# Power.net
KiCad netlist of a schematic drawn in Altium Designer
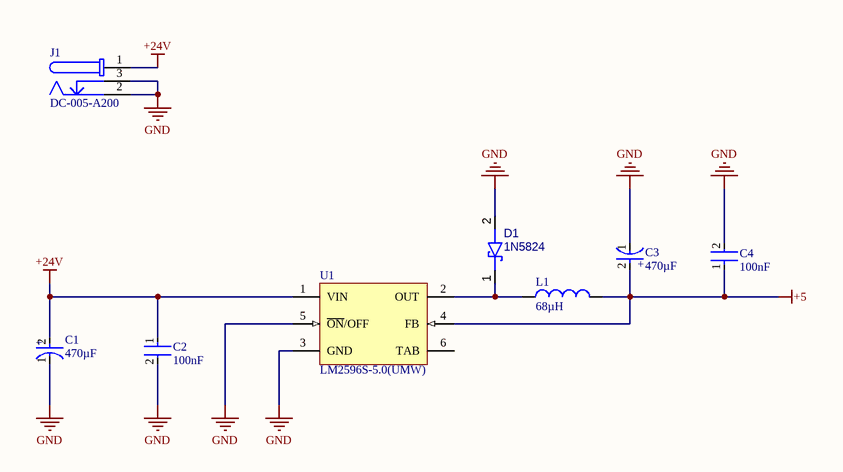
[diagram p0: Power.SchDoc]

(export (version "E")
  (design (tool "Eeschema 10.0.6"))
  (components
    (comp (ref "C1")
      (value "470µF")
      (footprint "FP-A750MV227M1HAAE020-MFG")
      (fields
        (field (name "TOLERANCE") "20%")
        (field (name "MANUFACTURER") "AISHI(Aihua Group)")
        (field (name "MFR.PART #") "ERS1VM471G16OT")
      )
      (libsource (lib "Hood") (part "a00bbbee19879c290e62620ae7e47b1"))
    )
    (comp (ref "C2")
      (value "100nF")
      (footprint "FP-CC0603-DA-IPC_B")
      (description "Multilayer Ceramic Capacitor, CC Series, 0.1 - F, - 10%, X7R, 50 V, 0603 [1608 Metric]")
      (fields (field (name "VOLTAGE") "50V") (field (name "TOLERANCE") "10%"))
      (libsource (lib "Hood") (part "11868f565c42a9108669ba33697ecf6"))
    )
    (comp (ref "C3")
      (value "470µF")
      (footprint "FP-A750MV227M1HAAE020-MFG")
      (fields (field (name "TOLERANCE") "20%") (field (name "Comment") "ERS1VM471G16OT"))
      (libsource (lib "Hood") (part "a00bbbee19879c290e62620ae7e47b1"))
    )
    (comp (ref "C4")
      (value "100nF")
      (footprint "FP-CC0603-DA-IPC_B")
      (description "Multilayer Ceramic Capacitor, CC Series, 0.1 - F, - 10%, X7R, 50 V, 0603 [1608 Metric]")
      (fields (field (name "VOLTAGE") "50V") (field (name "TOLERANCE") "10%"))
      (libsource (lib "Hood") (part "11868f565c42a9108669ba33697ecf6"))
    )
    (comp (ref "D1")
      (value "1N5824")
      (footprint "FP-017AF-MFG")
      (description "-55℃~+150℃ 150A 30V 500uA@30V 550mV@5A 5A Independent DO-201AD Schottky Diodes ROHS")
      (fields (field (name "MANUFACTURER") "FUXINSEMI") (field (name "JLCPCB PART #") "C7503125"))
      (libsource (lib "Hood") (part "DIODE-SKY-2"))
    )
    (comp (ref "J1")
      (value "DC-005-A200")
      (footprint "694108301002")
      (description "-20℃~+70℃ 2mm 30V 3A 6.4mm DC Power Jack Right Angle 插件 DC Power Connectors ROHS")
      (fields (field (name "JLCPCB PART #") "C720557") (field (name "MANUFACTURER") "XUNPU"))
      (libsource (lib "Hood") (part "DC Power Jack"))
    )
    (comp (ref "L1")
      (value "68µH")
      (footprint "CAPM115100X500N")
      (description "240mΩ 3A 4A 68uH Molded Inductor ±20% SMD,11.5x10mm Power Inductors ROHS")
      (fields (field (name "JLCPCB PART #") "C497902") (field (name "MFR.PART #") "YSPI1050-680M"))
      (libsource (lib "Hood") (part "IND-2"))
    )
    (comp (ref "U1")
      (value "LM2596S-5.0(UMW)")
      (footprint "KTT0005B_L")
      (fields
        (field (name "MANUFACTURER") "UMW(Youtai Semiconductor Co., Ltd.)")
        (field (name "JLCPCB PART #") "C347421")
      )
      (libsource (lib "Hood") (part "PM-REG-LM2575HVS-12"))
    )
  )
  (nets
    (net (code "1") (name "+5") (class "Default")
      (node (ref "C3") (pin "2") (pinfunction "A_2") (pintype "passive"))
      (node (ref "C4") (pin "1") (pinfunction "1_1") (pintype "passive"))
      (node (ref "L1") (pin "2") (pinfunction "2_2") (pintype "passive"))
      (node (ref "U1") (pin "4") (pinfunction "FB_4") (pintype "input"))
    )
    (net (code "2") (name "+24V") (class "Default")
      (node (ref "C1") (pin "2") (pinfunction "A_2") (pintype "passive"))
      (node (ref "C2") (pin "1") (pinfunction "1_1") (pintype "passive"))
      (node (ref "J1") (pin "1") (pinfunction "1_1") (pintype "passive"))
      (node (ref "U1") (pin "1") (pinfunction "VIN_1") (pintype "power_in"))
    )
    (net (code "3") (name "GND") (class "Default")
      (node (ref "C1") (pin "1") (pinfunction "C_1") (pintype "passive"))
      (node (ref "C2") (pin "2") (pinfunction "2_2") (pintype "passive"))
      (node (ref "C3") (pin "1") (pinfunction "C_1") (pintype "passive"))
      (node (ref "C4") (pin "2") (pinfunction "2_2") (pintype "passive"))
      (node (ref "D1") (pin "2") (pinfunction "A_2") (pintype "passive"))
      (node (ref "J1") (pin "2") (pinfunction "2_2") (pintype "passive"))
      (node (ref "J1") (pin "3") (pinfunction "3_3") (pintype "passive"))
      (node (ref "U1") (pin "3") (pinfunction "GND_3") (pintype "power_in"))
      (node (ref "U1") (pin "5") (pinfunction "~{ON}/OFF_5") (pintype "input"))
    )
    (net (code "4") (name "Net-(D1-K)") (class "Default")
      (node (ref "D1") (pin "1") (pinfunction "K_1") (pintype "passive"))
      (node (ref "L1") (pin "1") (pinfunction "1_1") (pintype "passive"))
      (node (ref "U1") (pin "2") (pinfunction "OUT_2") (pintype "power_in"))
    )
    (net (code "5") (name "unconnected-(U1-TAB-Pad6)") (class "Default")
      (node (ref "U1") (pin "6") (pinfunction "TAB_6") (pintype "power_in"))
    )
  )
)
